# ioShield-A.net
KiCad netlist of a schematic drawn in EAGLE
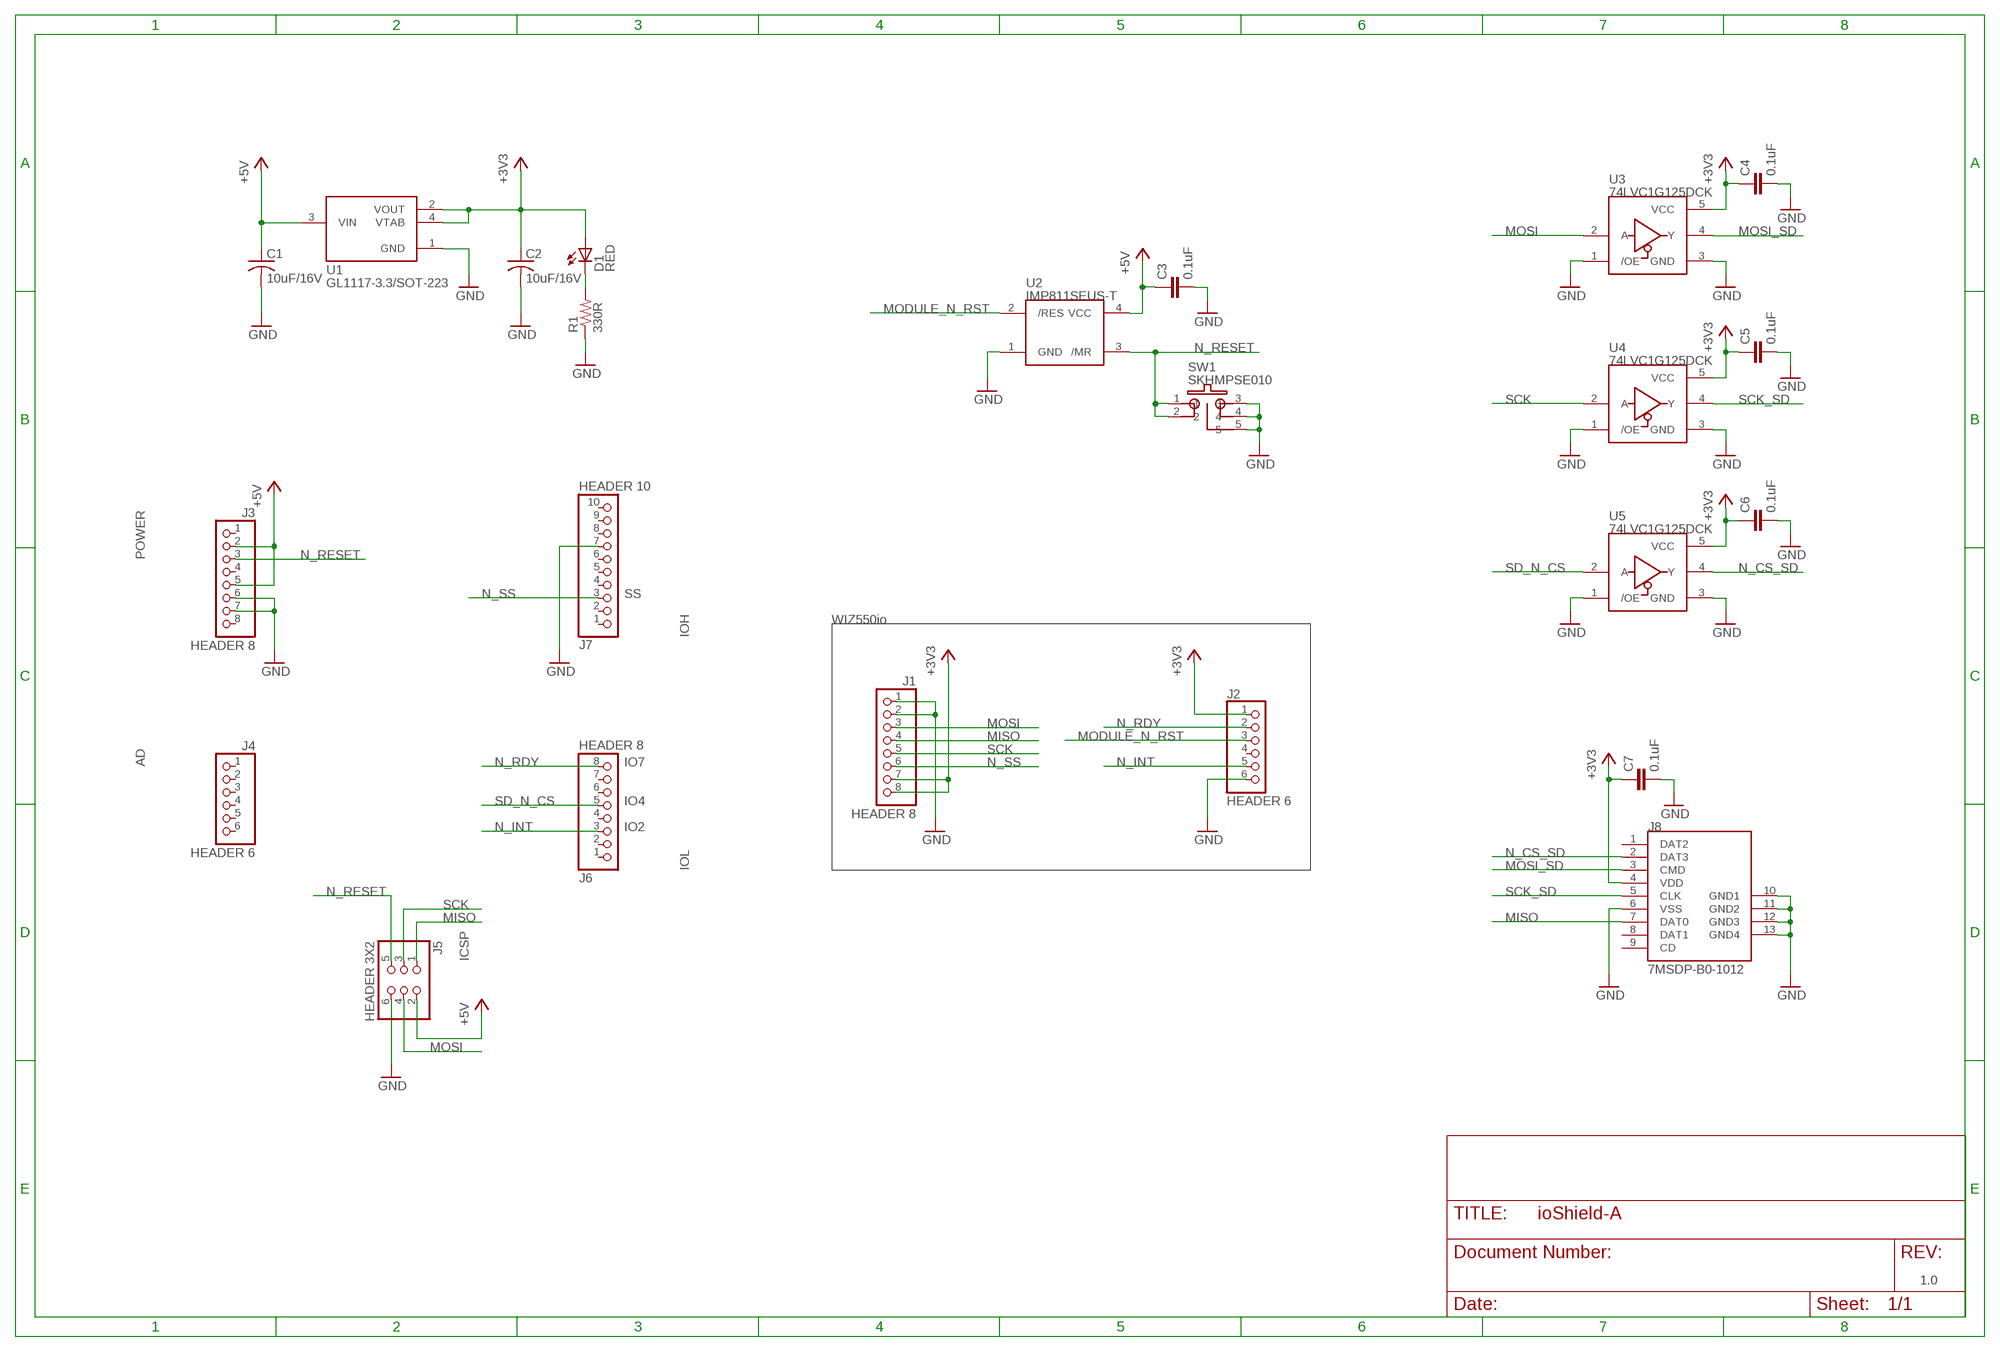
[diagram p0: schematic, sheet 1]

(export (version "E")
  (design (tool "Eeschema 10.0.6"))
  (components
    (comp (ref "C1")
      (value "10uF/16V")
      (footprint "eagle-import:CT-A(3216)")
      (libsource (lib "eagle-import") (part "CT-A(3216)"))
    )
    (comp (ref "C2")
      (value "10uF/16V")
      (footprint "eagle-import:CT-A(3216)")
      (libsource (lib "eagle-import") (part "CT-A(3216)"))
    )
    (comp (ref "C3")
      (value "0.1uF")
      (footprint "eagle-import:C1608")
      (libsource (lib "eagle-import") (part "C1608"))
    )
    (comp (ref "C4")
      (value "0.1uF")
      (footprint "eagle-import:C1608")
      (libsource (lib "eagle-import") (part "C1608"))
    )
    (comp (ref "C5")
      (value "0.1uF")
      (footprint "eagle-import:C1608")
      (libsource (lib "eagle-import") (part "C1608"))
    )
    (comp (ref "C6")
      (value "0.1uF")
      (footprint "eagle-import:C1608")
      (libsource (lib "eagle-import") (part "C1608"))
    )
    (comp (ref "C7")
      (value "0.1uF")
      (footprint "eagle-import:C1608")
      (libsource (lib "eagle-import") (part "C1608"))
    )
    (comp (ref "D1")
      (value "RED")
      (footprint "eagle-import:CHIP-LED1608")
      (libsource (lib "eagle-import") (part "LED1608"))
    )
    (comp (ref "J1")
      (value "HEADER 8")
      (footprint "eagle-import:HEADER1X8")
      (libsource (lib "eagle-import") (part "HEADER8"))
    )
    (comp (ref "J2")
      (value "HEADER 6")
      (footprint "eagle-import:HEADER1X6")
      (libsource (lib "eagle-import") (part "HEADER6"))
    )
    (comp (ref "J3")
      (value "HEADER 8")
      (footprint "eagle-import:HEADER1X8")
      (libsource (lib "eagle-import") (part "HEADER8"))
    )
    (comp (ref "J4")
      (value "HEADER 6")
      (footprint "eagle-import:HEADER1X6")
      (libsource (lib "eagle-import") (part "HEADER6"))
    )
    (comp (ref "J5")
      (value "HEADER 3X2")
      (footprint "eagle-import:HEADER3X2")
      (libsource (lib "eagle-import") (part "HEADER3X2"))
    )
    (comp (ref "J6")
      (value "HEADER 8")
      (footprint "eagle-import:HEADER1X8")
      (libsource (lib "eagle-import") (part "HEADER8"))
    )
    (comp (ref "J7")
      (value "HEADER 10")
      (footprint "eagle-import:HEADER1X10")
      (libsource (lib "eagle-import") (part "HEADER10"))
    )
    (comp (ref "J8")
      (value "7MSDP-B0-1012")
      (footprint "eagle-import:MICROSD_HC")
      (libsource (lib "eagle-import") (part "7MSDP-B0-1012"))
    )
    (comp (ref "R1")
      (value "330R")
      (footprint "eagle-import:R1608")
      (libsource (lib "eagle-import") (part "R1608"))
    )
    (comp (ref "SW1")
      (value "SKHMPSE010")
      (footprint "eagle-import:TACT_6.2X6.5")
      (libsource (lib "eagle-import") (part "TACT_6.2X6.5"))
    )
    (comp (ref "U1")
      (value "GL1117-3.3/SOT-223")
      (footprint "eagle-import:SOT223_HC")
      (libsource (lib "eagle-import") (part "GL1117-3.3/SOT-223"))
    )
    (comp (ref "U2")
      (value "IMP811SEUS-T")
      (footprint "eagle-import:SOT-143")
      (libsource (lib "eagle-import") (part "IMP811SEUS-T"))
    )
    (comp (ref "U3")
      (value "74LVC1G125DCK")
      (footprint "eagle-import:SC70-5(DCK)")
      (libsource (lib "eagle-import") (part "SN74LVC1G125"))
    )
    (comp (ref "U4")
      (value "74LVC1G125DCK")
      (footprint "eagle-import:SC70-5(DCK)")
      (libsource (lib "eagle-import") (part "SN74LVC1G125"))
    )
    (comp (ref "U5")
      (value "74LVC1G125DCK")
      (footprint "eagle-import:SC70-5(DCK)")
      (libsource (lib "eagle-import") (part "SN74LVC1G125"))
    )
  )
  (nets
    (net (code "1") (name "+3V3") (class "Default")
      (node (ref "C2") (pin "+") (pinfunction "1_+") (pintype "passive"))
      (node (ref "C4") (pin "1") (pinfunction "1_1") (pintype "passive"))
      (node (ref "C5") (pin "1") (pinfunction "1_1") (pintype "passive"))
      (node (ref "C6") (pin "1") (pinfunction "1_1") (pintype "passive"))
      (node (ref "C7") (pin "1") (pinfunction "1_1") (pintype "passive"))
      (node (ref "D1") (pin "A") (pinfunction "A_A") (pintype "passive"))
      (node (ref "J1") (pin "7") (pinfunction "7_7") (pintype "passive"))
      (node (ref "J1") (pin "8") (pinfunction "8_8") (pintype "passive"))
      (node (ref "J2") (pin "1") (pinfunction "1_1") (pintype "passive"))
      (node (ref "J8") (pin "4") (pinfunction "VDD_4") (pintype "passive"))
      (node (ref "U1") (pin "2") (pinfunction "VOUT_2") (pintype "passive"))
      (node (ref "U1") (pin "4") (pinfunction "VTAB_4") (pintype "passive"))
      (node (ref "U3") (pin "5") (pinfunction "VCC_5") (pintype "passive"))
      (node (ref "U4") (pin "5") (pinfunction "VCC_5") (pintype "passive"))
      (node (ref "U5") (pin "5") (pinfunction "VCC_5") (pintype "passive"))
    )
    (net (code "2") (name "+5V") (class "Default")
      (node (ref "C1") (pin "+") (pinfunction "1_+") (pintype "passive"))
      (node (ref "C3") (pin "1") (pinfunction "1_1") (pintype "passive"))
      (node (ref "J3") (pin "2") (pinfunction "2_2") (pintype "passive"))
      (node (ref "J3") (pin "5") (pinfunction "5_5") (pintype "passive"))
      (node (ref "J5") (pin "2") (pinfunction "2_2") (pintype "passive"))
      (node (ref "U1") (pin "3") (pinfunction "VIN_3") (pintype "passive"))
      (node (ref "U2") (pin "4") (pinfunction "VCC_4") (pintype "passive"))
    )
    (net (code "3") (name "/MISO") (class "Default")
      (node (ref "J1") (pin "4") (pinfunction "4_4") (pintype "passive"))
      (node (ref "J5") (pin "1") (pinfunction "1_1") (pintype "passive"))
      (node (ref "J8") (pin "7") (pinfunction "DAT0_7") (pintype "passive"))
    )
    (net (code "4") (name "/MODULE_N_RST") (class "Default")
      (node (ref "J2") (pin "3") (pinfunction "3_3") (pintype "passive"))
      (node (ref "U2") (pin "2") (pinfunction "/RES_2") (pintype "passive"))
    )
    (net (code "5") (name "/MOSI") (class "Default")
      (node (ref "J1") (pin "3") (pinfunction "3_3") (pintype "passive"))
      (node (ref "J5") (pin "4") (pinfunction "4_4") (pintype "passive"))
      (node (ref "U3") (pin "2") (pinfunction "A_2") (pintype "passive"))
    )
    (net (code "6") (name "/MOSI_SD") (class "Default")
      (node (ref "J8") (pin "3") (pinfunction "CMD_3") (pintype "passive"))
      (node (ref "U3") (pin "4") (pinfunction "Y_4") (pintype "passive"))
    )
    (net (code "7") (name "/N_CS_SD") (class "Default")
      (node (ref "J8") (pin "2") (pinfunction "DAT3_2") (pintype "passive"))
      (node (ref "U5") (pin "4") (pinfunction "Y_4") (pintype "passive"))
    )
    (net (code "8") (name "/N_INT") (class "Default")
      (node (ref "J2") (pin "5") (pinfunction "5_5") (pintype "passive"))
      (node (ref "J6") (pin "3") (pinfunction "3_3") (pintype "passive"))
    )
    (net (code "9") (name "/N_RDY") (class "Default")
      (node (ref "J2") (pin "2") (pinfunction "2_2") (pintype "passive"))
      (node (ref "J6") (pin "8") (pinfunction "8_8") (pintype "passive"))
    )
    (net (code "10") (name "/N_RESET") (class "Default")
      (node (ref "J3") (pin "3") (pinfunction "3_3") (pintype "passive"))
      (node (ref "J5") (pin "5") (pinfunction "5_5") (pintype "passive"))
      (node (ref "SW1") (pin "1") (pinfunction "1_1") (pintype "passive"))
      (node (ref "SW1") (pin "2") (pinfunction "2_2") (pintype "passive"))
      (node (ref "U2") (pin "3") (pinfunction "/MR_3") (pintype "passive"))
    )
    (net (code "11") (name "/N_SS") (class "Default")
      (node (ref "J1") (pin "6") (pinfunction "6_6") (pintype "passive"))
      (node (ref "J7") (pin "3") (pinfunction "3_3") (pintype "passive"))
    )
    (net (code "12") (name "/SCK") (class "Default")
      (node (ref "J1") (pin "5") (pinfunction "5_5") (pintype "passive"))
      (node (ref "J5") (pin "3") (pinfunction "3_3") (pintype "passive"))
      (node (ref "U4") (pin "2") (pinfunction "A_2") (pintype "passive"))
    )
    (net (code "13") (name "/SCK_SD") (class "Default")
      (node (ref "J8") (pin "5") (pinfunction "CLK_5") (pintype "passive"))
      (node (ref "U4") (pin "4") (pinfunction "Y_4") (pintype "passive"))
    )
    (net (code "14") (name "/SD_N_CS") (class "Default")
      (node (ref "J6") (pin "5") (pinfunction "5_5") (pintype "passive"))
      (node (ref "U5") (pin "2") (pinfunction "A_2") (pintype "passive"))
    )
    (net (code "15") (name "GND") (class "Default")
      (node (ref "C1") (pin "-") (pinfunction "2_-") (pintype "passive"))
      (node (ref "C2") (pin "-") (pinfunction "2_-") (pintype "passive"))
      (node (ref "C3") (pin "2") (pinfunction "2_2") (pintype "passive"))
      (node (ref "C4") (pin "2") (pinfunction "2_2") (pintype "passive"))
      (node (ref "C5") (pin "2") (pinfunction "2_2") (pintype "passive"))
      (node (ref "C6") (pin "2") (pinfunction "2_2") (pintype "passive"))
      (node (ref "C7") (pin "2") (pinfunction "2_2") (pintype "passive"))
      (node (ref "J1") (pin "1") (pinfunction "1_1") (pintype "passive"))
      (node (ref "J1") (pin "2") (pinfunction "2_2") (pintype "passive"))
      (node (ref "J2") (pin "6") (pinfunction "6_6") (pintype "passive"))
      (node (ref "J3") (pin "6") (pinfunction "6_6") (pintype "passive"))
      (node (ref "J3") (pin "7") (pinfunction "7_7") (pintype "passive"))
      (node (ref "J5") (pin "6") (pinfunction "6_6") (pintype "passive"))
      (node (ref "J7") (pin "7") (pinfunction "7_7") (pintype "passive"))
      (node (ref "J8") (pin "10") (pinfunction "GND1_10") (pintype "passive"))
      (node (ref "J8") (pin "11") (pinfunction "GND2_11") (pintype "passive"))
      (node (ref "J8") (pin "12") (pinfunction "GND3_12") (pintype "passive"))
      (node (ref "J8") (pin "13") (pinfunction "GND4_13") (pintype "passive"))
      (node (ref "J8") (pin "6") (pinfunction "VSS_6") (pintype "passive"))
      (node (ref "R1") (pin "1") (pinfunction "1_1") (pintype "passive"))
      (node (ref "SW1") (pin "3") (pinfunction "3_3") (pintype "passive"))
      (node (ref "SW1") (pin "4") (pinfunction "4_4") (pintype "passive"))
      (node (ref "SW1") (pin "5") (pinfunction "5_5") (pintype "passive"))
      (node (ref "U1") (pin "1") (pinfunction "GND_1") (pintype "passive"))
      (node (ref "U2") (pin "1") (pinfunction "GND_1") (pintype "passive"))
      (node (ref "U3") (pin "1") (pinfunction "/OE_1") (pintype "passive"))
      (node (ref "U3") (pin "3") (pinfunction "GND_3") (pintype "passive"))
      (node (ref "U4") (pin "1") (pinfunction "/OE_1") (pintype "passive"))
      (node (ref "U4") (pin "3") (pinfunction "GND_3") (pintype "passive"))
      (node (ref "U5") (pin "1") (pinfunction "/OE_1") (pintype "passive"))
      (node (ref "U5") (pin "3") (pinfunction "GND_3") (pintype "passive"))
    )
    (net (code "16") (name "Net-(D1-PadC)") (class "Default")
      (node (ref "D1") (pin "C") (pinfunction "C_C") (pintype "passive"))
      (node (ref "R1") (pin "2") (pinfunction "2_2") (pintype "passive"))
    )
    (net (code "17") (name "unconnected-(J2-Pad4)") (class "Default")
      (node (ref "J2") (pin "4") (pinfunction "4_4") (pintype "passive"))
    )
    (net (code "18") (name "unconnected-(J3-Pad1)") (class "Default")
      (node (ref "J3") (pin "1") (pinfunction "1_1") (pintype "passive"))
    )
    (net (code "19") (name "unconnected-(J3-Pad4)") (class "Default")
      (node (ref "J3") (pin "4") (pinfunction "4_4") (pintype "passive"))
    )
    (net (code "20") (name "unconnected-(J3-Pad8)") (class "Default")
      (node (ref "J3") (pin "8") (pinfunction "8_8") (pintype "passive"))
    )
    (net (code "21") (name "unconnected-(J4-Pad1)") (class "Default")
      (node (ref "J4") (pin "1") (pinfunction "1_1") (pintype "passive"))
    )
    (net (code "22") (name "unconnected-(J4-Pad2)") (class "Default")
      (node (ref "J4") (pin "2") (pinfunction "2_2") (pintype "passive"))
    )
    (net (code "23") (name "unconnected-(J4-Pad3)") (class "Default")
      (node (ref "J4") (pin "3") (pinfunction "3_3") (pintype "passive"))
    )
    (net (code "24") (name "unconnected-(J4-Pad4)") (class "Default")
      (node (ref "J4") (pin "4") (pinfunction "4_4") (pintype "passive"))
    )
    (net (code "25") (name "unconnected-(J4-Pad5)") (class "Default")
      (node (ref "J4") (pin "5") (pinfunction "5_5") (pintype "passive"))
    )
    (net (code "26") (name "unconnected-(J4-Pad6)") (class "Default")
      (node (ref "J4") (pin "6") (pinfunction "6_6") (pintype "passive"))
    )
    (net (code "27") (name "unconnected-(J6-Pad1)") (class "Default")
      (node (ref "J6") (pin "1") (pinfunction "1_1") (pintype "passive"))
    )
    (net (code "28") (name "unconnected-(J6-Pad2)") (class "Default")
      (node (ref "J6") (pin "2") (pinfunction "2_2") (pintype "passive"))
    )
    (net (code "29") (name "unconnected-(J6-Pad4)") (class "Default")
      (node (ref "J6") (pin "4") (pinfunction "4_4") (pintype "passive"))
    )
    (net (code "30") (name "unconnected-(J6-Pad6)") (class "Default")
      (node (ref "J6") (pin "6") (pinfunction "6_6") (pintype "passive"))
    )
    (net (code "31") (name "unconnected-(J6-Pad7)") (class "Default")
      (node (ref "J6") (pin "7") (pinfunction "7_7") (pintype "passive"))
    )
    (net (code "32") (name "unconnected-(J7-Pad1)") (class "Default")
      (node (ref "J7") (pin "1") (pinfunction "1_1") (pintype "passive"))
    )
    (net (code "33") (name "unconnected-(J7-Pad2)") (class "Default")
      (node (ref "J7") (pin "2") (pinfunction "2_2") (pintype "passive"))
    )
    (net (code "34") (name "unconnected-(J7-Pad4)") (class "Default")
      (node (ref "J7") (pin "4") (pinfunction "4_4") (pintype "passive"))
    )
    (net (code "35") (name "unconnected-(J7-Pad5)") (class "Default")
      (node (ref "J7") (pin "5") (pinfunction "5_5") (pintype "passive"))
    )
    (net (code "36") (name "unconnected-(J7-Pad6)") (class "Default")
      (node (ref "J7") (pin "6") (pinfunction "6_6") (pintype "passive"))
    )
    (net (code "37") (name "unconnected-(J7-Pad8)") (class "Default")
      (node (ref "J7") (pin "8") (pinfunction "8_8") (pintype "passive"))
    )
    (net (code "38") (name "unconnected-(J7-Pad9)") (class "Default")
      (node (ref "J7") (pin "9") (pinfunction "9_9") (pintype "passive"))
    )
    (net (code "39") (name "unconnected-(J7-Pad10)") (class "Default")
      (node (ref "J7") (pin "10") (pinfunction "10_10") (pintype "passive"))
    )
    (net (code "40") (name "unconnected-(J8-CD-Pad9)") (class "Default")
      (node (ref "J8") (pin "9") (pinfunction "CD_9") (pintype "passive"))
    )
    (net (code "41") (name "unconnected-(J8-DAT1-Pad8)") (class "Default")
      (node (ref "J8") (pin "8") (pinfunction "DAT1_8") (pintype "passive"))
    )
    (net (code "42") (name "unconnected-(J8-DAT2-Pad1)") (class "Default")
      (node (ref "J8") (pin "1") (pinfunction "DAT2_1") (pintype "passive"))
    )
  )
)
